# GSRv2_1.net
KiCad netlist of a schematic drawn in EAGLE
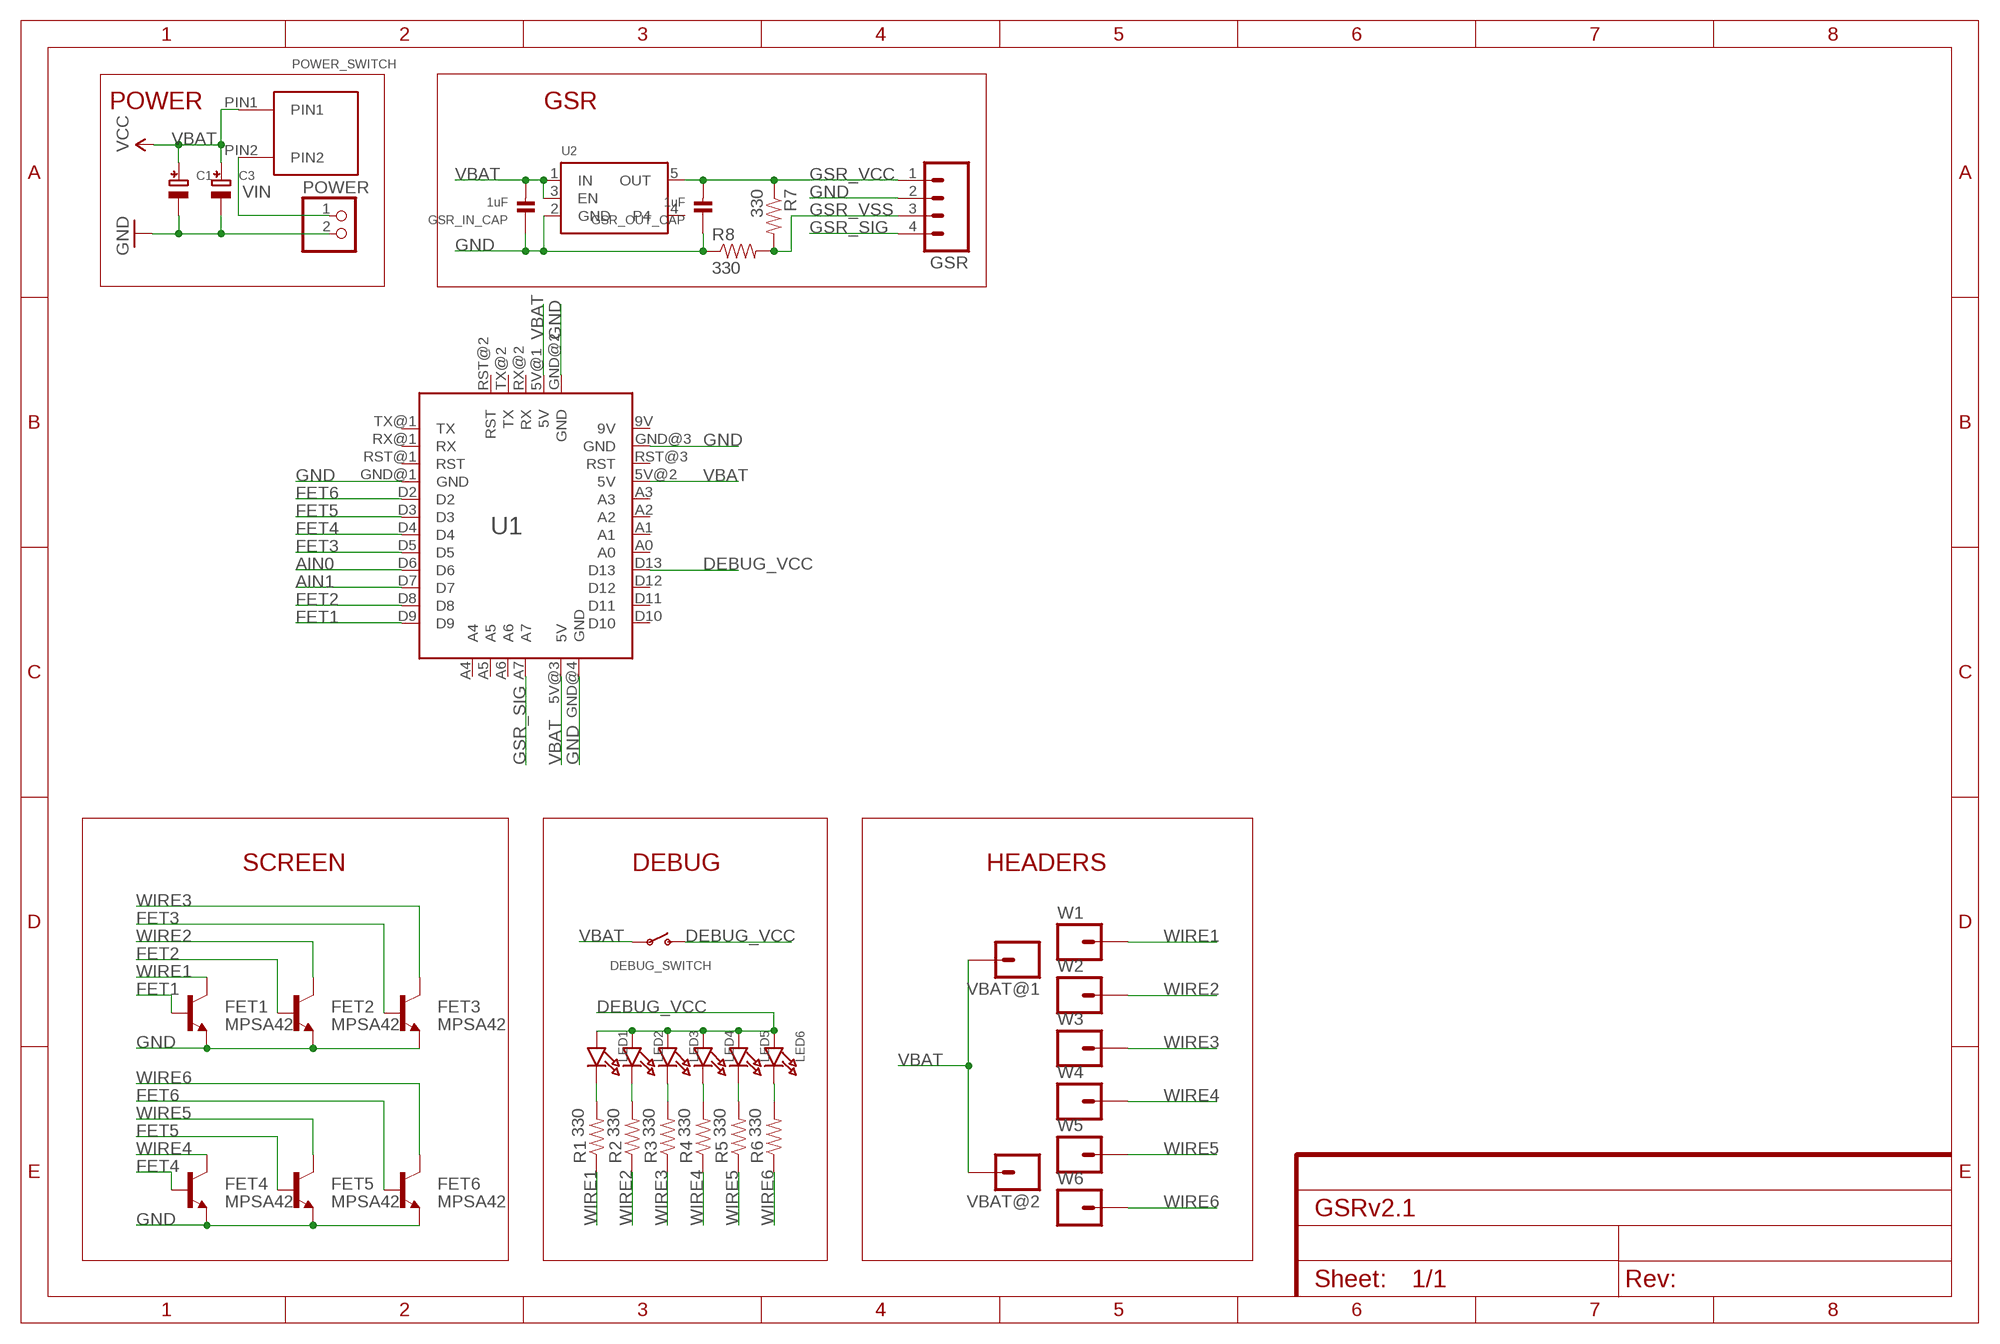
[diagram p0: schematic, sheet 1]

(export (version "E")
  (design (tool "Eeschema 10.0.6"))
  (components
    (comp (ref "C1")
      (value "CAP_TANTALUMB/3528_WAVE")
      (footprint "eagle-import:EIA3528-21_B-W")
      (libsource (lib "eagle-import") (part "CAP_TANTALUMB/3528_WAVE"))
    )
    (comp (ref "C3")
      (value "CAP_TANTALUMB/3528_WAVE")
      (footprint "eagle-import:EIA3528-21_B-W")
      (libsource (lib "eagle-import") (part "CAP_TANTALUMB/3528_WAVE"))
    )
    (comp (ref "DEBUG_SWITCH")
      (value "SWITCH_SPST")
      (footprint "eagle-import:SPST_SMT_19192")
      (libsource (lib "eagle-import") (part "SWITCH_SPST"))
    )
    (comp (ref "FET1")
      (value "MPSA42")
      (footprint "eagle-import:SOT23-3")
      (libsource (lib "eagle-import") (part "TRANSISTOR_NPNMPSA42"))
    )
    (comp (ref "FET2")
      (value "MPSA42")
      (footprint "eagle-import:SOT23-3")
      (libsource (lib "eagle-import") (part "TRANSISTOR_NPNMPSA42"))
    )
    (comp (ref "FET3")
      (value "MPSA42")
      (footprint "eagle-import:SOT23-3")
      (libsource (lib "eagle-import") (part "TRANSISTOR_NPNMPSA42"))
    )
    (comp (ref "FET4")
      (value "MPSA42")
      (footprint "eagle-import:SOT23-3")
      (libsource (lib "eagle-import") (part "TRANSISTOR_NPNMPSA42"))
    )
    (comp (ref "FET5")
      (value "MPSA42")
      (footprint "eagle-import:SOT23-3")
      (libsource (lib "eagle-import") (part "TRANSISTOR_NPNMPSA42"))
    )
    (comp (ref "FET6")
      (value "MPSA42")
      (footprint "eagle-import:SOT23-3")
      (libsource (lib "eagle-import") (part "TRANSISTOR_NPNMPSA42"))
    )
    (comp (ref "GSR")
      (value "M04PTH")
      (footprint "eagle-import:1X04")
      (libsource (lib "eagle-import") (part "M04PTH"))
    )
    (comp (ref "GSR_IN_CAP")
      (value "1uF")
      (footprint "eagle-import:0603")
      (libsource (lib "eagle-import") (part "CAP_CERAMIC0603"))
    )
    (comp (ref "GSR_OUT_CAP")
      (value "1uF")
      (footprint "eagle-import:0603")
      (libsource (lib "eagle-import") (part "CAP_CERAMIC0603"))
    )
    (comp (ref "LED1")
      (value "LED0603_NOOUTLINE")
      (footprint "eagle-import:CHIPLED_0603_NOOUTLINE")
      (libsource (lib "eagle-import") (part "LED0603_NOOUTLINE"))
    )
    (comp (ref "LED2")
      (value "LED0603_NOOUTLINE")
      (footprint "eagle-import:CHIPLED_0603_NOOUTLINE")
      (libsource (lib "eagle-import") (part "LED0603_NOOUTLINE"))
    )
    (comp (ref "LED3")
      (value "LED0603_NOOUTLINE")
      (footprint "eagle-import:CHIPLED_0603_NOOUTLINE")
      (libsource (lib "eagle-import") (part "LED0603_NOOUTLINE"))
    )
    (comp (ref "LED4")
      (value "LED0603_NOOUTLINE")
      (footprint "eagle-import:CHIPLED_0603_NOOUTLINE")
      (libsource (lib "eagle-import") (part "LED0603_NOOUTLINE"))
    )
    (comp (ref "LED5")
      (value "LED0603_NOOUTLINE")
      (footprint "eagle-import:CHIPLED_0603_NOOUTLINE")
      (libsource (lib "eagle-import") (part "LED0603_NOOUTLINE"))
    )
    (comp (ref "LED6")
      (value "LED0603_NOOUTLINE")
      (footprint "eagle-import:CHIPLED_0603_NOOUTLINE")
      (libsource (lib "eagle-import") (part "LED0603_NOOUTLINE"))
    )
    (comp (ref "POWER")
      (value "JST_2PIN")
      (footprint "eagle-import:JSTPH2")
      (libsource (lib "eagle-import") (part "JST_2PIN"))
    )
    (comp (ref "POWER_SWITCH")
      (value "PUSH_BUTTON")
      (footprint "eagle-import:PUSH_BUTTON")
      (libsource (lib "eagle-import") (part "PUSH_BUTTON"))
    )
    (comp (ref "R1")
      (value "330")
      (footprint "eagle-import:0603-RES")
      (libsource (lib "eagle-import") (part "RESISTOR0603-RES"))
    )
    (comp (ref "R2")
      (value "330")
      (footprint "eagle-import:0603-RES")
      (libsource (lib "eagle-import") (part "RESISTOR0603-RES"))
    )
    (comp (ref "R3")
      (value "330")
      (footprint "eagle-import:0603-RES")
      (libsource (lib "eagle-import") (part "RESISTOR0603-RES"))
    )
    (comp (ref "R4")
      (value "330")
      (footprint "eagle-import:0603-RES")
      (libsource (lib "eagle-import") (part "RESISTOR0603-RES"))
    )
    (comp (ref "R5")
      (value "330")
      (footprint "eagle-import:0603-RES")
      (libsource (lib "eagle-import") (part "RESISTOR0603-RES"))
    )
    (comp (ref "R6")
      (value "330")
      (footprint "eagle-import:0603-RES")
      (libsource (lib "eagle-import") (part "RESISTOR0603-RES"))
    )
    (comp (ref "R7")
      (value "330")
      (footprint "eagle-import:0603")
      (libsource (lib "eagle-import") (part "0OHM-1/10W-5%(0603)"))
    )
    (comp (ref "R8")
      (value "330")
      (footprint "eagle-import:0603")
      (libsource (lib "eagle-import") (part "0OHM-1/10W-5%(0603)"))
    )
    (comp (ref "U1")
      (value "ARDUINO_MINI")
      (footprint "eagle-import:ARDUINO_MINI")
      (libsource (lib "eagle-import") (part "ARDUINO_MINI"))
    )
    (comp (ref "U2")
      (value "VREG_SOT23-5")
      (footprint "eagle-import:SOT23-5")
      (libsource (lib "eagle-import") (part "VREG_SOT23-5"))
    )
    (comp (ref "VBAT@1")
      (value "M01NOSILK-KIT")
      (footprint "eagle-import:1X01NS-KIT")
      (libsource (lib "eagle-import") (part "M01NOSILK-KIT"))
    )
    (comp (ref "VBAT@2")
      (value "M01NOSILK-KIT")
      (footprint "eagle-import:1X01NS-KIT")
      (libsource (lib "eagle-import") (part "M01NOSILK-KIT"))
    )
    (comp (ref "W1")
      (value "M01NOSILK-KIT")
      (footprint "eagle-import:1X01NS-KIT")
      (libsource (lib "eagle-import") (part "M01NOSILK-KIT"))
    )
    (comp (ref "W2")
      (value "M01NOSILK-KIT")
      (footprint "eagle-import:1X01NS-KIT")
      (libsource (lib "eagle-import") (part "M01NOSILK-KIT"))
    )
    (comp (ref "W3")
      (value "M01NOSILK-KIT")
      (footprint "eagle-import:1X01NS-KIT")
      (libsource (lib "eagle-import") (part "M01NOSILK-KIT"))
    )
    (comp (ref "W4")
      (value "M01NOSILK-KIT")
      (footprint "eagle-import:1X01NS-KIT")
      (libsource (lib "eagle-import") (part "M01NOSILK-KIT"))
    )
    (comp (ref "W5")
      (value "M01NOSILK-KIT")
      (footprint "eagle-import:1X01NS-KIT")
      (libsource (lib "eagle-import") (part "M01NOSILK-KIT"))
    )
    (comp (ref "W6")
      (value "M01NOSILK-KIT")
      (footprint "eagle-import:1X01NS-KIT")
      (libsource (lib "eagle-import") (part "M01NOSILK-KIT"))
    )
  )
  (nets
    (net (code "1") (name "/9V") (class "Default")
      (node (ref "U1") (pin "9V") (pinfunction "9V_9V") (pintype "power_in"))
    )
    (net (code "2") (name "/AIN0") (class "Default")
      (node (ref "U1") (pin "D6") (pinfunction "D6_D6") (pintype "bidirectional"))
    )
    (net (code "3") (name "/AIN1") (class "Default")
      (node (ref "U1") (pin "D7") (pinfunction "D7_D7") (pintype "bidirectional"))
    )
    (net (code "4") (name "/DEBUG_VCC") (class "Default")
      (node (ref "DEBUG_SWITCH") (pin "C") (pinfunction "S_C") (pintype "passive"))
      (node (ref "LED1") (pin "A") (pinfunction "A_A") (pintype "passive"))
      (node (ref "LED2") (pin "A") (pinfunction "A_A") (pintype "passive"))
      (node (ref "LED3") (pin "A") (pinfunction "A_A") (pintype "passive"))
      (node (ref "LED4") (pin "A") (pinfunction "A_A") (pintype "passive"))
      (node (ref "LED5") (pin "A") (pinfunction "A_A") (pintype "passive"))
      (node (ref "LED6") (pin "A") (pinfunction "A_A") (pintype "passive"))
      (node (ref "U1") (pin "D13") (pinfunction "D13_D13") (pintype "bidirectional"))
    )
    (net (code "5") (name "/FET1") (class "Default")
      (node (ref "FET1") (pin "1") (pinfunction "B_1") (pintype "passive"))
      (node (ref "U1") (pin "D9") (pinfunction "D9_D9") (pintype "bidirectional"))
    )
    (net (code "6") (name "/FET2") (class "Default")
      (node (ref "FET2") (pin "1") (pinfunction "B_1") (pintype "passive"))
      (node (ref "U1") (pin "D8") (pinfunction "D8_D8") (pintype "bidirectional"))
    )
    (net (code "7") (name "/FET3") (class "Default")
      (node (ref "FET3") (pin "1") (pinfunction "B_1") (pintype "passive"))
      (node (ref "U1") (pin "D5") (pinfunction "D5_D5") (pintype "bidirectional"))
    )
    (net (code "8") (name "/FET4") (class "Default")
      (node (ref "FET4") (pin "1") (pinfunction "B_1") (pintype "passive"))
      (node (ref "U1") (pin "D4") (pinfunction "D4_D4") (pintype "bidirectional"))
    )
    (net (code "9") (name "/FET5") (class "Default")
      (node (ref "FET5") (pin "1") (pinfunction "B_1") (pintype "passive"))
      (node (ref "U1") (pin "D3") (pinfunction "D3_D3") (pintype "bidirectional"))
    )
    (net (code "10") (name "/FET6") (class "Default")
      (node (ref "FET6") (pin "1") (pinfunction "B_1") (pintype "passive"))
      (node (ref "U1") (pin "D2") (pinfunction "D2_D2") (pintype "bidirectional"))
    )
    (net (code "11") (name "/GSR_SIG") (class "Default")
      (node (ref "GSR") (pin "4") (pinfunction "4_4") (pintype "passive"))
      (node (ref "U1") (pin "A7") (pinfunction "A7_A7") (pintype "bidirectional"))
    )
    (net (code "12") (name "/GSR_VCC") (class "Default")
      (node (ref "GSR") (pin "1") (pinfunction "1_1") (pintype "passive"))
      (node (ref "GSR_OUT_CAP") (pin "2") (pinfunction "P$2_2") (pintype "passive"))
      (node (ref "R7") (pin "1") (pinfunction "1_1") (pintype "passive"))
      (node (ref "U2") (pin "5") (pinfunction "OUT_5") (pintype "bidirectional"))
    )
    (net (code "13") (name "/GSR_VSS") (class "Default")
      (node (ref "GSR") (pin "3") (pinfunction "3_3") (pintype "passive"))
      (node (ref "R7") (pin "2") (pinfunction "2_2") (pintype "passive"))
      (node (ref "R8") (pin "2") (pinfunction "2_2") (pintype "passive"))
    )
    (net (code "14") (name "/VIN") (class "Default")
      (node (ref "POWER") (pin "1") (pinfunction "1_1") (pintype "passive"))
      (node (ref "POWER_SWITCH") (pin "PIN2") (pinfunction "PIN2_PIN2") (pintype "bidirectional"))
    )
    (net (code "15") (name "/WIRE1") (class "Default")
      (node (ref "FET1") (pin "3") (pinfunction "C_3") (pintype "passive"))
      (node (ref "R1") (pin "1") (pinfunction "1_1") (pintype "passive"))
      (node (ref "W1") (pin "1") (pinfunction "1_1") (pintype "passive"))
    )
    (net (code "16") (name "/WIRE2") (class "Default")
      (node (ref "FET2") (pin "3") (pinfunction "C_3") (pintype "passive"))
      (node (ref "R2") (pin "1") (pinfunction "1_1") (pintype "passive"))
      (node (ref "W2") (pin "1") (pinfunction "1_1") (pintype "passive"))
    )
    (net (code "17") (name "/WIRE3") (class "Default")
      (node (ref "FET3") (pin "3") (pinfunction "C_3") (pintype "passive"))
      (node (ref "R3") (pin "1") (pinfunction "1_1") (pintype "passive"))
      (node (ref "W3") (pin "1") (pinfunction "1_1") (pintype "passive"))
    )
    (net (code "18") (name "/WIRE4") (class "Default")
      (node (ref "FET4") (pin "3") (pinfunction "C_3") (pintype "passive"))
      (node (ref "R4") (pin "1") (pinfunction "1_1") (pintype "passive"))
      (node (ref "W4") (pin "1") (pinfunction "1_1") (pintype "passive"))
    )
    (net (code "19") (name "/WIRE5") (class "Default")
      (node (ref "FET5") (pin "3") (pinfunction "C_3") (pintype "passive"))
      (node (ref "R5") (pin "1") (pinfunction "1_1") (pintype "passive"))
      (node (ref "W5") (pin "1") (pinfunction "1_1") (pintype "passive"))
    )
    (net (code "20") (name "/WIRE6") (class "Default")
      (node (ref "FET6") (pin "3") (pinfunction "C_3") (pintype "passive"))
      (node (ref "R6") (pin "1") (pinfunction "1_1") (pintype "passive"))
      (node (ref "W6") (pin "1") (pinfunction "1_1") (pintype "passive"))
    )
    (net (code "21") (name "GND") (class "Default")
      (node (ref "C1") (pin "-") (pinfunction "-_-") (pintype "passive"))
      (node (ref "C3") (pin "-") (pinfunction "-_-") (pintype "passive"))
      (node (ref "FET1") (pin "2") (pinfunction "E_2") (pintype "passive"))
      (node (ref "FET2") (pin "2") (pinfunction "E_2") (pintype "passive"))
      (node (ref "FET3") (pin "2") (pinfunction "E_2") (pintype "passive"))
      (node (ref "FET4") (pin "2") (pinfunction "E_2") (pintype "passive"))
      (node (ref "FET5") (pin "2") (pinfunction "E_2") (pintype "passive"))
      (node (ref "FET6") (pin "2") (pinfunction "E_2") (pintype "passive"))
      (node (ref "GSR") (pin "2") (pinfunction "2_2") (pintype "passive"))
      (node (ref "GSR_IN_CAP") (pin "1") (pinfunction "P$1_1") (pintype "passive"))
      (node (ref "GSR_OUT_CAP") (pin "1") (pinfunction "P$1_1") (pintype "passive"))
      (node (ref "POWER") (pin "2") (pinfunction "2_2") (pintype "passive"))
      (node (ref "R8") (pin "1") (pinfunction "1_1") (pintype "passive"))
      (node (ref "U1") (pin "GND@1") (pinfunction "GND_GND@1") (pintype "power_in"))
      (node (ref "U1") (pin "GND@2") (pinfunction "GND_GND@2") (pintype "power_in"))
      (node (ref "U1") (pin "GND@3") (pinfunction "GND_GND@3") (pintype "power_in"))
      (node (ref "U1") (pin "GND@4") (pinfunction "GND_GND@4") (pintype "power_in"))
      (node (ref "U2") (pin "2") (pinfunction "GND_2") (pintype "bidirectional"))
    )
    (net (code "22") (name "Net-(LED1-PadC)") (class "Default")
      (node (ref "LED1") (pin "C") (pinfunction "C_C") (pintype "passive"))
      (node (ref "R1") (pin "2") (pinfunction "2_2") (pintype "passive"))
    )
    (net (code "23") (name "Net-(LED2-PadC)") (class "Default")
      (node (ref "LED2") (pin "C") (pinfunction "C_C") (pintype "passive"))
      (node (ref "R2") (pin "2") (pinfunction "2_2") (pintype "passive"))
    )
    (net (code "24") (name "Net-(LED3-PadC)") (class "Default")
      (node (ref "LED3") (pin "C") (pinfunction "C_C") (pintype "passive"))
      (node (ref "R3") (pin "2") (pinfunction "2_2") (pintype "passive"))
    )
    (net (code "25") (name "Net-(LED4-PadC)") (class "Default")
      (node (ref "LED4") (pin "C") (pinfunction "C_C") (pintype "passive"))
      (node (ref "R4") (pin "2") (pinfunction "2_2") (pintype "passive"))
    )
    (net (code "26") (name "Net-(LED5-PadC)") (class "Default")
      (node (ref "LED5") (pin "C") (pinfunction "C_C") (pintype "passive"))
      (node (ref "R5") (pin "2") (pinfunction "2_2") (pintype "passive"))
    )
    (net (code "27") (name "Net-(LED6-PadC)") (class "Default")
      (node (ref "LED6") (pin "C") (pinfunction "C_C") (pintype "passive"))
      (node (ref "R6") (pin "2") (pinfunction "2_2") (pintype "passive"))
    )
    (net (code "28") (name "VCC") (class "Default")
      (node (ref "C1") (pin "+") (pinfunction "+_+") (pintype "passive"))
      (node (ref "C3") (pin "+") (pinfunction "+_+") (pintype "passive"))
      (node (ref "DEBUG_SWITCH") (pin "B") (pinfunction "P_B") (pintype "passive"))
      (node (ref "GSR_IN_CAP") (pin "2") (pinfunction "P$2_2") (pintype "passive"))
      (node (ref "POWER_SWITCH") (pin "PIN1") (pinfunction "PIN1_PIN1") (pintype "bidirectional"))
      (node (ref "U1") (pin "5V@1") (pinfunction "5V_5V@1") (pintype "power_in"))
      (node (ref "U1") (pin "5V@2") (pinfunction "5V_5V@2") (pintype "power_in"))
      (node (ref "U1") (pin "5V@3") (pinfunction "5V_5V@3") (pintype "power_in"))
      (node (ref "U2") (pin "1") (pinfunction "IN_1") (pintype "bidirectional"))
      (node (ref "U2") (pin "3") (pinfunction "EN_3") (pintype "bidirectional"))
      (node (ref "VBAT@1") (pin "1") (pinfunction "1_1") (pintype "passive"))
      (node (ref "VBAT@2") (pin "1") (pinfunction "1_1") (pintype "passive"))
    )
    (net (code "29") (name "unconnected-(U1-PadA0)") (class "Default")
      (node (ref "U1") (pin "A0") (pinfunction "A0_A0") (pintype "bidirectional"))
    )
    (net (code "30") (name "unconnected-(U1-PadA1)") (class "Default")
      (node (ref "U1") (pin "A1") (pinfunction "A1_A1") (pintype "bidirectional"))
    )
    (net (code "31") (name "unconnected-(U1-PadA2)") (class "Default")
      (node (ref "U1") (pin "A2") (pinfunction "A2_A2") (pintype "bidirectional"))
    )
    (net (code "32") (name "unconnected-(U1-PadA3)") (class "Default")
      (node (ref "U1") (pin "A3") (pinfunction "A3_A3") (pintype "bidirectional"))
    )
    (net (code "33") (name "unconnected-(U1-PadA4)") (class "Default")
      (node (ref "U1") (pin "A4") (pinfunction "A4_A4") (pintype "bidirectional"))
    )
    (net (code "34") (name "unconnected-(U1-PadA5)") (class "Default")
      (node (ref "U1") (pin "A5") (pinfunction "A5_A5") (pintype "bidirectional"))
    )
    (net (code "35") (name "unconnected-(U1-PadA6)") (class "Default")
      (node (ref "U1") (pin "A6") (pinfunction "A6_A6") (pintype "bidirectional"))
    )
    (net (code "36") (name "unconnected-(U1-PadD10)") (class "Default")
      (node (ref "U1") (pin "D10") (pinfunction "D10_D10") (pintype "bidirectional"))
    )
    (net (code "37") (name "unconnected-(U1-PadD11)") (class "Default")
      (node (ref "U1") (pin "D11") (pinfunction "D11_D11") (pintype "bidirectional"))
    )
    (net (code "38") (name "unconnected-(U1-PadD12)") (class "Default")
      (node (ref "U1") (pin "D12") (pinfunction "D12_D12") (pintype "bidirectional"))
    )
    (net (code "39") (name "unconnected-(U1-RST-PadRST@1)") (class "Default")
      (node (ref "U1") (pin "RST@1") (pinfunction "RST_RST@1") (pintype "bidirectional"))
    )
    (net (code "40") (name "unconnected-(U1-RST-PadRST@2)") (class "Default")
      (node (ref "U1") (pin "RST@2") (pinfunction "RST_RST@2") (pintype "bidirectional"))
    )
    (net (code "41") (name "unconnected-(U1-RST-PadRST@3)") (class "Default")
      (node (ref "U1") (pin "RST@3") (pinfunction "RST_RST@3") (pintype "bidirectional"))
    )
    (net (code "42") (name "unconnected-(U1-RX-PadRX@1)") (class "Default")
      (node (ref "U1") (pin "RX@1") (pinfunction "RX_RX@1") (pintype "bidirectional"))
    )
    (net (code "43") (name "unconnected-(U1-RX-PadRX@2)") (class "Default")
      (node (ref "U1") (pin "RX@2") (pinfunction "RX_RX@2") (pintype "bidirectional"))
    )
    (net (code "44") (name "unconnected-(U1-TX-PadTX@1)") (class "Default")
      (node (ref "U1") (pin "TX@1") (pinfunction "TX_TX@1") (pintype "bidirectional"))
    )
    (net (code "45") (name "unconnected-(U1-TX-PadTX@2)") (class "Default")
      (node (ref "U1") (pin "TX@2") (pinfunction "TX_TX@2") (pintype "bidirectional"))
    )
    (net (code "46") (name "unconnected-(U2-P4-Pad4)") (class "Default")
      (node (ref "U2") (pin "4") (pinfunction "P4_4") (pintype "bidirectional"))
    )
  )
)
